# ADRF6780Dev.net
KiCad netlist of a schematic drawn in Altium Designer
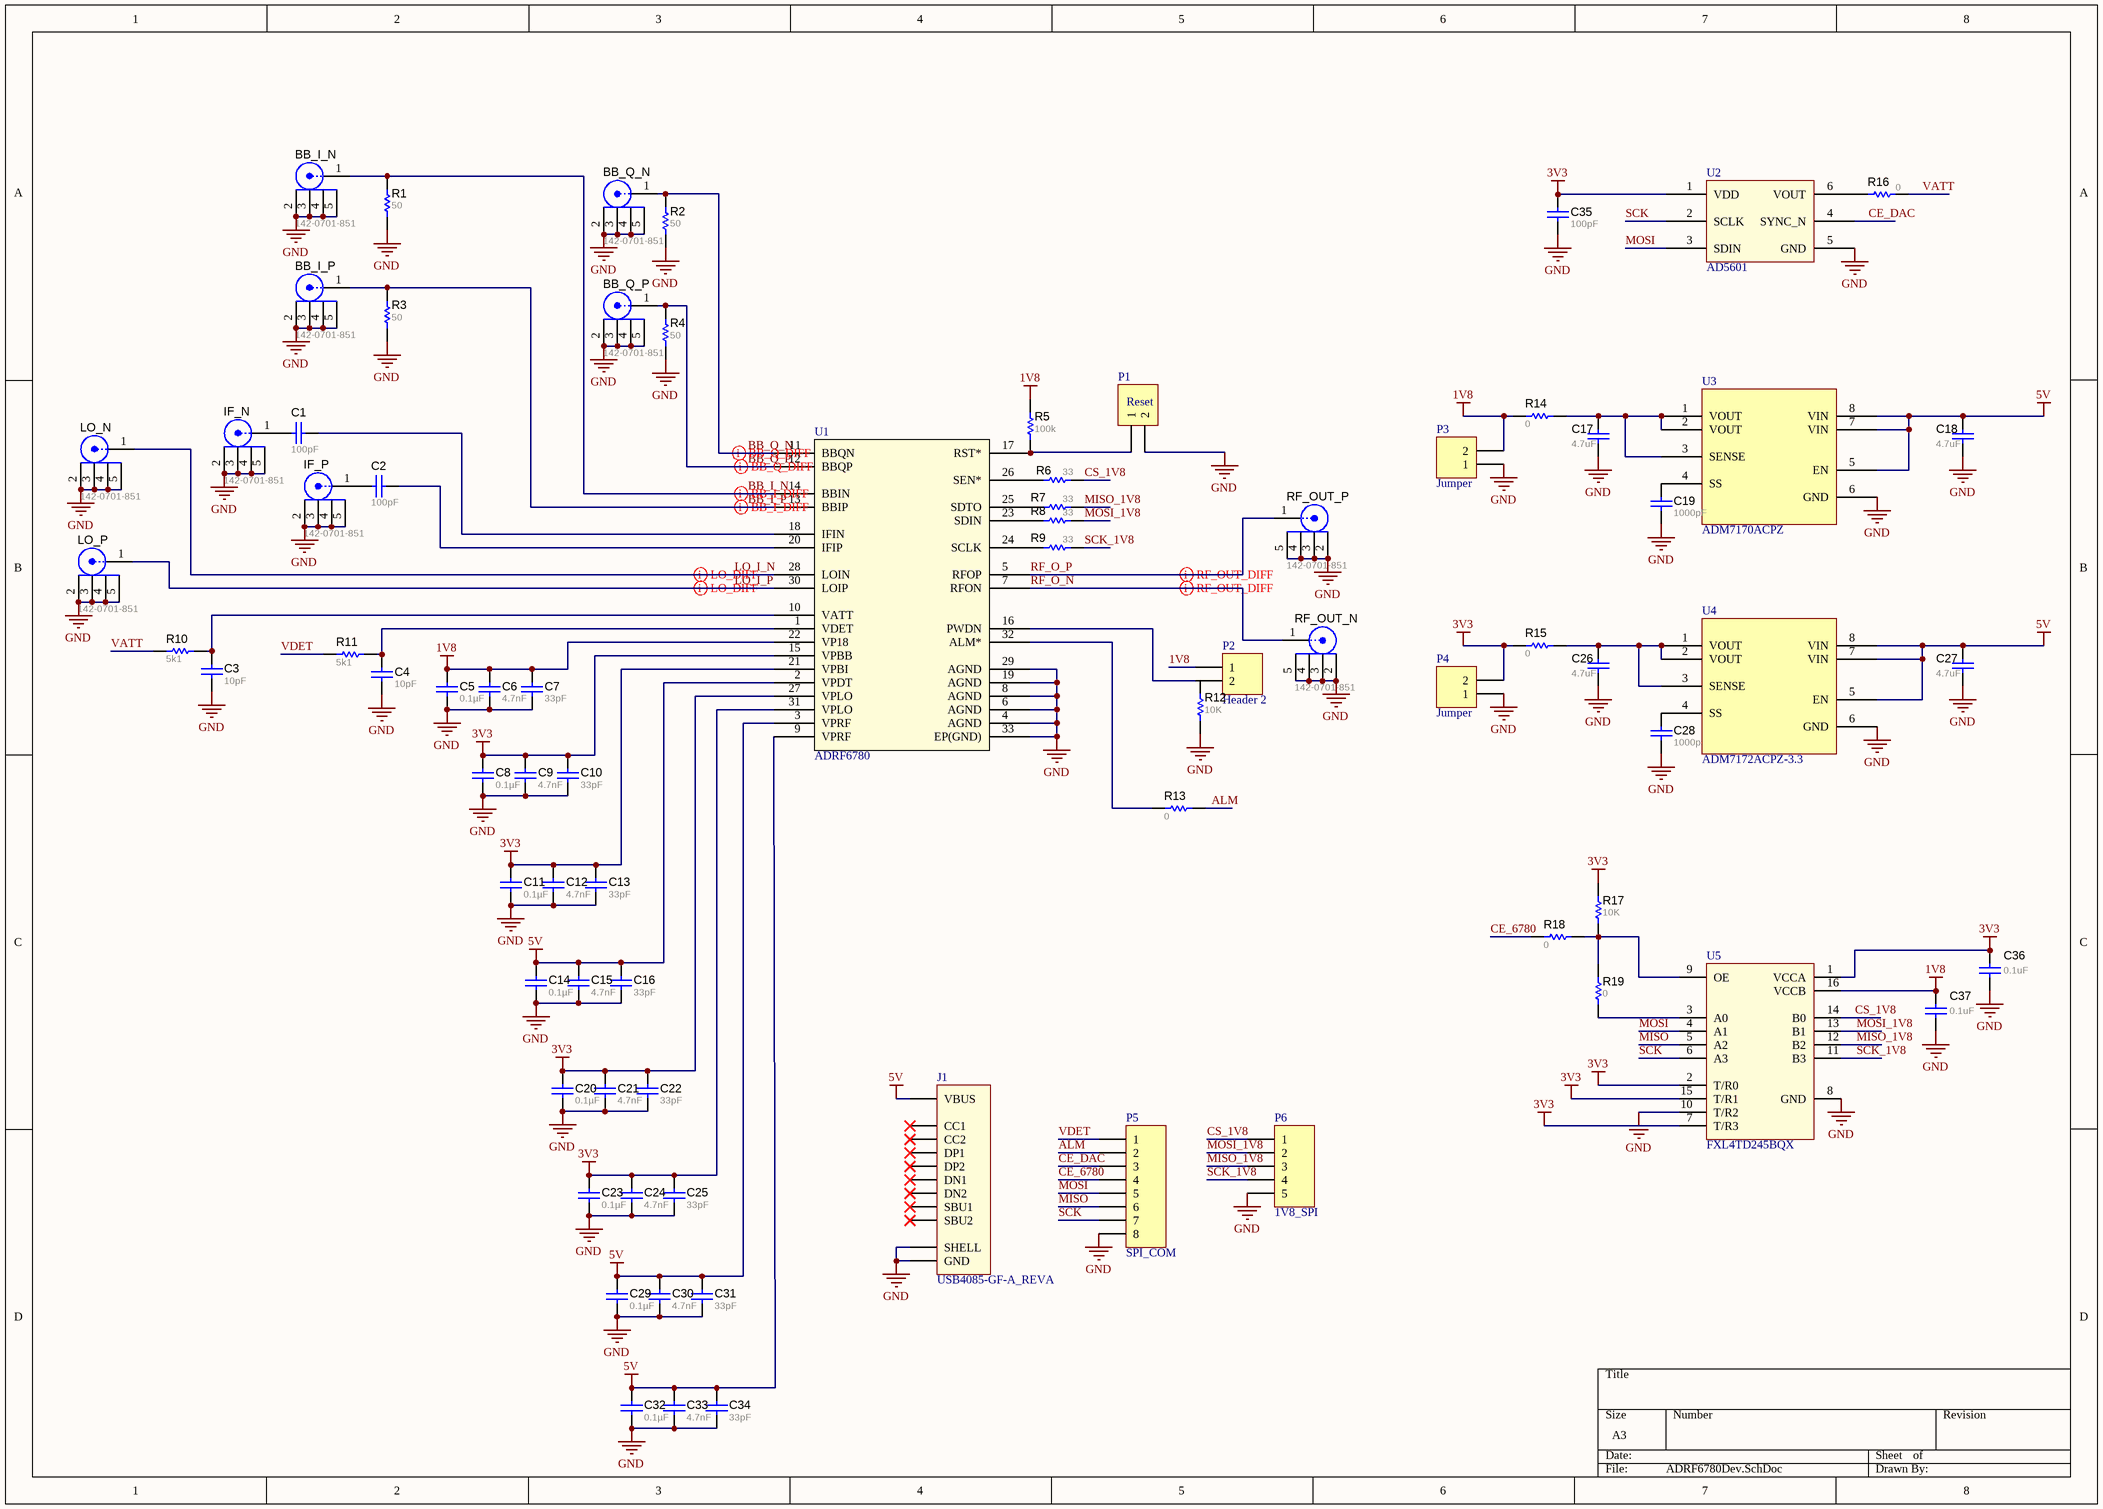
[diagram p0: ADRF6780Dev.SchDoc]

(export (version "E")
  (design (tool "Eeschema 10.0.6"))
  (components
    (comp (ref "BB_I_N")
      (value "142-0701-851")
      (footprint "Emerson_142-0701-851")
      (description "Connector, SMT, End launch SMA 50 ohm")
      (fields
        (field (name "MANUFACTURER") "Emerson Network Power Connectivity")
        (field (name "DIGIKEYPARTNUMBER") "J658-ND")
        (field (name "PUBLISHER") "National Semiconductor")
      )
      (libsource (lib "SV601308") (part "142-0701-851"))
    )
    (comp (ref "BB_I_P")
      (value "142-0701-851")
      (footprint "Emerson_142-0701-851")
      (description "Connector, SMT, End launch SMA 50 ohm")
      (fields
        (field (name "MANUFACTURER") "Emerson Network Power Connectivity")
        (field (name "DIGIKEYPARTNUMBER") "J658-ND")
        (field (name "PUBLISHER") "National Semiconductor")
      )
      (libsource (lib "SV601308") (part "142-0701-851"))
    )
    (comp (ref "BB_Q_N")
      (value "142-0701-851")
      (footprint "Emerson_142-0701-851")
      (description "Connector, SMT, End launch SMA 50 ohm")
      (fields
        (field (name "MANUFACTURER") "Emerson Network Power Connectivity")
        (field (name "DIGIKEYPARTNUMBER") "J658-ND")
        (field (name "PUBLISHER") "National Semiconductor")
      )
      (libsource (lib "SV601308") (part "142-0701-851"))
    )
    (comp (ref "BB_Q_P")
      (value "142-0701-851")
      (footprint "Emerson_142-0701-851")
      (description "Connector, SMT, End launch SMA 50 ohm")
      (fields
        (field (name "MANUFACTURER") "Emerson Network Power Connectivity")
        (field (name "DIGIKEYPARTNUMBER") "J658-ND")
        (field (name "PUBLISHER") "National Semiconductor")
      )
      (libsource (lib "SV601308") (part "142-0701-851"))
    )
    (comp (ref "C1")
      (value "C0603C101J5GACTU")
      (footprint "0603")
      (description "CAP, CERM, 100 pF, 50 V, +/- 5%, C0G/NP0, 0603")
      (fields
        (field (name "MANUFACTURER") "Kemet")
        (field (name "VALUEDISPLAYED") "100pF")
        (field (name "PUBLISHER") "Texas Instruments")
      )
      (libsource (lib "SV601308") (part "C0603C101J5GACTU"))
    )
    (comp (ref "C2")
      (value "C0603C101J5GACTU")
      (footprint "0603")
      (description "CAP, CERM, 100 pF, 50 V, +/- 5%, C0G/NP0, 0603")
      (fields
        (field (name "MANUFACTURER") "Kemet")
        (field (name "VALUEDISPLAYED") "100pF")
        (field (name "PUBLISHER") "Texas Instruments")
      )
      (libsource (lib "SV601308") (part "C0603C101J5GACTU"))
    )
    (comp (ref "C3")
      (value "C1608X5R1A106M080AC")
      (footprint "0603")
      (description "CAP, CERM, 10 µF, 10 V, +/- 20%, X5R, 0603")
      (fields
        (field (name "MANUFACTURER") "TDK")
        (field (name "VALUEDISPLAYED") "10pF")
        (field (name "PUBLISHER") "Texas Instruments")
      )
      (libsource (lib "SV601308") (part "C1608X5R1A106M080AC"))
    )
    (comp (ref "C4")
      (value "C1608X5R1A106M080AC")
      (footprint "0603")
      (description "CAP, CERM, 10 µF, 10 V, +/- 20%, X5R, 0603")
      (fields
        (field (name "MANUFACTURER") "TDK")
        (field (name "VALUEDISPLAYED") "10pF")
        (field (name "PUBLISHER") "Texas Instruments")
      )
      (libsource (lib "SV601308") (part "C1608X5R1A106M080AC"))
    )
    (comp (ref "C5")
      (value "C1608X5R1A106M080AC")
      (footprint "0603")
      (description "CAP, CERM, 10 µF, 10 V, +/- 20%, X5R, 0603")
      (fields
        (field (name "MANUFACTURER") "TDK")
        (field (name "VALUEDISPLAYED") "0.1µF")
        (field (name "PUBLISHER") "Texas Instruments")
      )
      (libsource (lib "SV601308") (part "C1608X5R1A106M080AC"))
    )
    (comp (ref "C6")
      (value "C1608X5R1A106M080AC")
      (footprint "0603")
      (description "CAP, CERM, 10 µF, 10 V, +/- 20%, X5R, 0603")
      (fields
        (field (name "MANUFACTURER") "TDK")
        (field (name "VALUEDISPLAYED") "4.7nF")
        (field (name "PUBLISHER") "Texas Instruments")
      )
      (libsource (lib "SV601308") (part "C1608X5R1A106M080AC"))
    )
    (comp (ref "C7")
      (value "C1608X5R1A106M080AC")
      (footprint "0603")
      (description "CAP, CERM, 10 µF, 10 V, +/- 20%, X5R, 0603")
      (fields
        (field (name "MANUFACTURER") "TDK")
        (field (name "VALUEDISPLAYED") "33pF")
        (field (name "PUBLISHER") "Texas Instruments")
      )
      (libsource (lib "SV601308") (part "C1608X5R1A106M080AC"))
    )
    (comp (ref "C8")
      (value "C1608X5R1A106M080AC")
      (footprint "0603")
      (description "CAP, CERM, 10 µF, 10 V, +/- 20%, X5R, 0603")
      (fields
        (field (name "MANUFACTURER") "TDK")
        (field (name "VALUEDISPLAYED") "0.1µF")
        (field (name "PUBLISHER") "Texas Instruments")
      )
      (libsource (lib "SV601308") (part "C1608X5R1A106M080AC"))
    )
    (comp (ref "C9")
      (value "C1608X5R1A106M080AC")
      (footprint "0603")
      (description "CAP, CERM, 10 µF, 10 V, +/- 20%, X5R, 0603")
      (fields
        (field (name "MANUFACTURER") "TDK")
        (field (name "VALUEDISPLAYED") "4.7nF")
        (field (name "PUBLISHER") "Texas Instruments")
      )
      (libsource (lib "SV601308") (part "C1608X5R1A106M080AC"))
    )
    (comp (ref "C10")
      (value "C1608X5R1A106M080AC")
      (footprint "0603")
      (description "CAP, CERM, 10 µF, 10 V, +/- 20%, X5R, 0603")
      (fields
        (field (name "MANUFACTURER") "TDK")
        (field (name "VALUEDISPLAYED") "33pF")
        (field (name "PUBLISHER") "Texas Instruments")
      )
      (libsource (lib "SV601308") (part "C1608X5R1A106M080AC"))
    )
    (comp (ref "C11")
      (value "C1608X5R1A106M080AC")
      (footprint "0603")
      (description "CAP, CERM, 10 µF, 10 V, +/- 20%, X5R, 0603")
      (fields
        (field (name "MANUFACTURER") "TDK")
        (field (name "VALUEDISPLAYED") "0.1µF")
        (field (name "PUBLISHER") "Texas Instruments")
      )
      (libsource (lib "SV601308") (part "C1608X5R1A106M080AC"))
    )
    (comp (ref "C12")
      (value "C1608X5R1A106M080AC")
      (footprint "0603")
      (description "CAP, CERM, 10 µF, 10 V, +/- 20%, X5R, 0603")
      (fields
        (field (name "MANUFACTURER") "TDK")
        (field (name "VALUEDISPLAYED") "4.7nF")
        (field (name "PUBLISHER") "Texas Instruments")
      )
      (libsource (lib "SV601308") (part "C1608X5R1A106M080AC"))
    )
    (comp (ref "C13")
      (value "C1608X5R1A106M080AC")
      (footprint "0603")
      (description "CAP, CERM, 10 µF, 10 V, +/- 20%, X5R, 0603")
      (fields
        (field (name "MANUFACTURER") "TDK")
        (field (name "VALUEDISPLAYED") "33pF")
        (field (name "PUBLISHER") "Texas Instruments")
      )
      (libsource (lib "SV601308") (part "C1608X5R1A106M080AC"))
    )
    (comp (ref "C14")
      (value "C1608X5R1A106M080AC")
      (footprint "0603")
      (description "CAP, CERM, 10 µF, 10 V, +/- 20%, X5R, 0603")
      (fields
        (field (name "MANUFACTURER") "TDK")
        (field (name "VALUEDISPLAYED") "0.1µF")
        (field (name "PUBLISHER") "Texas Instruments")
      )
      (libsource (lib "SV601308") (part "C1608X5R1A106M080AC"))
    )
    (comp (ref "C15")
      (value "C1608X5R1A106M080AC")
      (footprint "0603")
      (description "CAP, CERM, 10 µF, 10 V, +/- 20%, X5R, 0603")
      (fields
        (field (name "MANUFACTURER") "TDK")
        (field (name "VALUEDISPLAYED") "4.7nF")
        (field (name "PUBLISHER") "Texas Instruments")
      )
      (libsource (lib "SV601308") (part "C1608X5R1A106M080AC"))
    )
    (comp (ref "C16")
      (value "C1608X5R1A106M080AC")
      (footprint "0603")
      (description "CAP, CERM, 10 µF, 10 V, +/- 20%, X5R, 0603")
      (fields
        (field (name "MANUFACTURER") "TDK")
        (field (name "VALUEDISPLAYED") "33pF")
        (field (name "PUBLISHER") "Texas Instruments")
      )
      (libsource (lib "SV601308") (part "C1608X5R1A106M080AC"))
    )
    (comp (ref "C17")
      (value "C0603C472J5RACTU")
      (footprint "0603")
      (description "CAP, CERM, 4700 pF, 50 V, +/- 5%, X7R, 0603")
      (fields
        (field (name "MANUFACTURER") "Kemet")
        (field (name "VALUEDISPLAYED") "4.7uF")
        (field (name "PUBLISHER") "Texas Instruments")
      )
      (libsource (lib "SV601308") (part "C0603C472J5RACTU"))
    )
    (comp (ref "C18")
      (value "C0603C472J5RACTU")
      (footprint "0603")
      (description "CAP, CERM, 4700 pF, 50 V, +/- 5%, X7R, 0603")
      (fields
        (field (name "MANUFACTURER") "Kemet")
        (field (name "VALUEDISPLAYED") "4.7uF")
        (field (name "PUBLISHER") "Texas Instruments")
      )
      (libsource (lib "SV601308") (part "C0603C472J5RACTU"))
    )
    (comp (ref "C19")
      (value "C0603C472J5RACTU")
      (footprint "0603")
      (description "CAP, CERM, 4700 pF, 50 V, +/- 5%, X7R, 0603")
      (fields
        (field (name "MANUFACTURER") "Kemet")
        (field (name "VALUEDISPLAYED") "1000pF")
        (field (name "PUBLISHER") "Texas Instruments")
      )
      (libsource (lib "SV601308") (part "C0603C472J5RACTU"))
    )
    (comp (ref "C20")
      (value "C1608X5R1A106M080AC")
      (footprint "0603")
      (description "CAP, CERM, 10 µF, 10 V, +/- 20%, X5R, 0603")
      (fields
        (field (name "MANUFACTURER") "TDK")
        (field (name "VALUEDISPLAYED") "0.1µF")
        (field (name "PUBLISHER") "Texas Instruments")
      )
      (libsource (lib "SV601308") (part "C1608X5R1A106M080AC"))
    )
    (comp (ref "C21")
      (value "C1608X5R1A106M080AC")
      (footprint "0603")
      (description "CAP, CERM, 10 µF, 10 V, +/- 20%, X5R, 0603")
      (fields
        (field (name "MANUFACTURER") "TDK")
        (field (name "VALUEDISPLAYED") "4.7nF")
        (field (name "PUBLISHER") "Texas Instruments")
      )
      (libsource (lib "SV601308") (part "C1608X5R1A106M080AC"))
    )
    (comp (ref "C22")
      (value "C1608X5R1A106M080AC")
      (footprint "0603")
      (description "CAP, CERM, 10 µF, 10 V, +/- 20%, X5R, 0603")
      (fields
        (field (name "MANUFACTURER") "TDK")
        (field (name "VALUEDISPLAYED") "33pF")
        (field (name "PUBLISHER") "Texas Instruments")
      )
      (libsource (lib "SV601308") (part "C1608X5R1A106M080AC"))
    )
    (comp (ref "C23")
      (value "C1608X5R1A106M080AC")
      (footprint "0603")
      (description "CAP, CERM, 10 µF, 10 V, +/- 20%, X5R, 0603")
      (fields
        (field (name "MANUFACTURER") "TDK")
        (field (name "VALUEDISPLAYED") "0.1µF")
        (field (name "PUBLISHER") "Texas Instruments")
      )
      (libsource (lib "SV601308") (part "C1608X5R1A106M080AC"))
    )
    (comp (ref "C24")
      (value "C1608X5R1A106M080AC")
      (footprint "0603")
      (description "CAP, CERM, 10 µF, 10 V, +/- 20%, X5R, 0603")
      (fields
        (field (name "MANUFACTURER") "TDK")
        (field (name "VALUEDISPLAYED") "4.7nF")
        (field (name "PUBLISHER") "Texas Instruments")
      )
      (libsource (lib "SV601308") (part "C1608X5R1A106M080AC"))
    )
    (comp (ref "C25")
      (value "C1608X5R1A106M080AC")
      (footprint "0603")
      (description "CAP, CERM, 10 µF, 10 V, +/- 20%, X5R, 0603")
      (fields
        (field (name "MANUFACTURER") "TDK")
        (field (name "VALUEDISPLAYED") "33pF")
        (field (name "PUBLISHER") "Texas Instruments")
      )
      (libsource (lib "SV601308") (part "C1608X5R1A106M080AC"))
    )
    (comp (ref "C26")
      (value "C0603C472J5RACTU")
      (footprint "0603")
      (description "CAP, CERM, 4700 pF, 50 V, +/- 5%, X7R, 0603")
      (fields
        (field (name "MANUFACTURER") "Kemet")
        (field (name "VALUEDISPLAYED") "4.7uF")
        (field (name "PUBLISHER") "Texas Instruments")
      )
      (libsource (lib "SV601308") (part "C0603C472J5RACTU"))
    )
    (comp (ref "C27")
      (value "C0603C472J5RACTU")
      (footprint "0603")
      (description "CAP, CERM, 4700 pF, 50 V, +/- 5%, X7R, 0603")
      (fields
        (field (name "MANUFACTURER") "Kemet")
        (field (name "VALUEDISPLAYED") "4.7uF")
        (field (name "PUBLISHER") "Texas Instruments")
      )
      (libsource (lib "SV601308") (part "C0603C472J5RACTU"))
    )
    (comp (ref "C28")
      (value "C0603C472J5RACTU")
      (footprint "0603")
      (description "CAP, CERM, 4700 pF, 50 V, +/- 5%, X7R, 0603")
      (fields
        (field (name "MANUFACTURER") "Kemet")
        (field (name "VALUEDISPLAYED") "1000pF")
        (field (name "PUBLISHER") "Texas Instruments")
      )
      (libsource (lib "SV601308") (part "C0603C472J5RACTU"))
    )
    (comp (ref "C29")
      (value "C1608X5R1A106M080AC")
      (footprint "0603")
      (description "CAP, CERM, 10 µF, 10 V, +/- 20%, X5R, 0603")
      (fields
        (field (name "MANUFACTURER") "TDK")
        (field (name "VALUEDISPLAYED") "0.1µF")
        (field (name "PUBLISHER") "Texas Instruments")
      )
      (libsource (lib "SV601308") (part "C1608X5R1A106M080AC"))
    )
    (comp (ref "C30")
      (value "C1608X5R1A106M080AC")
      (footprint "0603")
      (description "CAP, CERM, 10 µF, 10 V, +/- 20%, X5R, 0603")
      (fields
        (field (name "MANUFACTURER") "TDK")
        (field (name "VALUEDISPLAYED") "4.7nF")
        (field (name "PUBLISHER") "Texas Instruments")
      )
      (libsource (lib "SV601308") (part "C1608X5R1A106M080AC"))
    )
    (comp (ref "C31")
      (value "C1608X5R1A106M080AC")
      (footprint "0603")
      (description "CAP, CERM, 10 µF, 10 V, +/- 20%, X5R, 0603")
      (fields
        (field (name "MANUFACTURER") "TDK")
        (field (name "VALUEDISPLAYED") "33pF")
        (field (name "PUBLISHER") "Texas Instruments")
      )
      (libsource (lib "SV601308") (part "C1608X5R1A106M080AC"))
    )
    (comp (ref "C32")
      (value "C1608X5R1A106M080AC")
      (footprint "0603")
      (description "CAP, CERM, 10 µF, 10 V, +/- 20%, X5R, 0603")
      (fields
        (field (name "MANUFACTURER") "TDK")
        (field (name "VALUEDISPLAYED") "0.1µF")
        (field (name "PUBLISHER") "Texas Instruments")
      )
      (libsource (lib "SV601308") (part "C1608X5R1A106M080AC"))
    )
    (comp (ref "C33")
      (value "C1608X5R1A106M080AC")
      (footprint "0603")
      (description "CAP, CERM, 10 µF, 10 V, +/- 20%, X5R, 0603")
      (fields
        (field (name "MANUFACTURER") "TDK")
        (field (name "VALUEDISPLAYED") "4.7nF")
        (field (name "PUBLISHER") "Texas Instruments")
      )
      (libsource (lib "SV601308") (part "C1608X5R1A106M080AC"))
    )
    (comp (ref "C34")
      (value "C1608X5R1A106M080AC")
      (footprint "0603")
      (description "CAP, CERM, 10 µF, 10 V, +/- 20%, X5R, 0603")
      (fields
        (field (name "MANUFACTURER") "TDK")
        (field (name "VALUEDISPLAYED") "33pF")
        (field (name "PUBLISHER") "Texas Instruments")
      )
      (libsource (lib "SV601308") (part "C1608X5R1A106M080AC"))
    )
    (comp (ref "C35")
      (value "C0603C101J5GACTU")
      (footprint "0603")
      (description "CAP, CERM, 100 pF, 50 V, +/- 5%, C0G/NP0, 0603")
      (fields
        (field (name "MANUFACTURER") "Kemet")
        (field (name "VALUEDISPLAYED") "100pF")
        (field (name "PUBLISHER") "Texas Instruments")
      )
      (libsource (lib "SV601308") (part "C0603C101J5GACTU"))
    )
    (comp (ref "C36")
      (value "C0603C472J5RACTU")
      (footprint "0603")
      (description "CAP, CERM, 4700 pF, 50 V, +/- 5%, X7R, 0603")
      (fields
        (field (name "MANUFACTURER") "Kemet")
        (field (name "VALUEDISPLAYED") "0.1uF")
        (field (name "PUBLISHER") "Texas Instruments")
      )
      (libsource (lib "SV601308") (part "C0603C472J5RACTU"))
    )
    (comp (ref "C37")
      (value "C0603C472J5RACTU")
      (footprint "0603")
      (description "CAP, CERM, 4700 pF, 50 V, +/- 5%, X7R, 0603")
      (fields
        (field (name "MANUFACTURER") "Kemet")
        (field (name "VALUEDISPLAYED") "0.1uF")
        (field (name "PUBLISHER") "Texas Instruments")
      )
      (libsource (lib "SV601308") (part "C0603C472J5RACTU"))
    )
    (comp (ref "IF_N")
      (value "142-0701-851")
      (footprint "Emerson_142-0701-851")
      (description "Connector, SMT, End launch SMA 50 ohm")
      (fields
        (field (name "MANUFACTURER") "Emerson Network Power Connectivity")
        (field (name "DIGIKEYPARTNUMBER") "J658-ND")
        (field (name "PUBLISHER") "National Semiconductor")
      )
      (libsource (lib "SV601308") (part "142-0701-851"))
    )
    (comp (ref "IF_P")
      (value "142-0701-851")
      (footprint "Emerson_142-0701-851")
      (description "Connector, SMT, End launch SMA 50 ohm")
      (fields
        (field (name "MANUFACTURER") "Emerson Network Power Connectivity")
        (field (name "DIGIKEYPARTNUMBER") "J658-ND")
        (field (name "PUBLISHER") "National Semiconductor")
      )
      (libsource (lib "SV601308") (part "142-0701-851"))
    )
    (comp (ref "J1")
      (value "USB4085-GF-A_REVA")
      (footprint "GCT_USB4085-GF-A_REVA")
      (fields (field (name "MP") "USB4085-GF-A") (field (name "MF") "Global Connector Technology"))
      (libsource (lib "USB4085-GF-A_REVA") (part "USB4085-GF-A_REVA"))
    )
    (comp (ref "LO_N")
      (value "142-0701-851")
      (footprint "Emerson_142-0701-851")
      (description "Connector, SMT, End launch SMA 50 ohm")
      (fields
        (field (name "MANUFACTURER") "Emerson Network Power Connectivity")
        (field (name "DIGIKEYPARTNUMBER") "J658-ND")
        (field (name "PUBLISHER") "National Semiconductor")
      )
      (libsource (lib "SV601308") (part "142-0701-851"))
    )
    (comp (ref "LO_P")
      (value "142-0701-851")
      (footprint "Emerson_142-0701-851")
      (description "Connector, SMT, End launch SMA 50 ohm")
      (fields
        (field (name "MANUFACTURER") "Emerson Network Power Connectivity")
        (field (name "DIGIKEYPARTNUMBER") "J658-ND")
        (field (name "PUBLISHER") "National Semiconductor")
      )
      (libsource (lib "SV601308") (part "142-0701-851"))
    )
    (comp (ref "P1")
      (value "Reset")
      (footprint "HDR1X2")
      (description "Header, 2-Pin")
      (fields (field (name "PUBLISHER") "Altium Limited"))
      (libsource (lib "Miscellaneous Connectors") (part "Header 2"))
    )
    (comp (ref "P2")
      (value "Header 2")
      (footprint "HDR1X2")
      (description "Header, 2-Pin")
      (fields (field (name "PUBLISHER") "Altium Limited"))
      (libsource (lib "") (part "Header 2_2"))
    )
    (comp (ref "P3")
      (value "Jumper")
      (footprint "HDR1X2")
      (description "Header, 2-Pin")
      (fields (field (name "PUBLISHER") "Altium Limited"))
      (libsource (lib "") (part "Header 2_1"))
    )
    (comp (ref "P4")
      (value "Jumper")
      (footprint "HDR1X2")
      (description "Header, 2-Pin")
      (fields (field (name "PUBLISHER") "Altium Limited"))
      (libsource (lib "") (part "Header 2_1"))
    )
    (comp (ref "P5")
      (value "SPI_COM")
      (footprint "HDR1X8")
      (description "Header, 8-Pin")
      (fields (field (name "PUBLISHER") "Altium Limited"))
      (libsource (lib "Miscellaneous Connectors") (part "Header 8"))
    )
    (comp (ref "P6")
      (value "1V8_SPI")
      (footprint "HDR1X5")
      (description "Header, 5-Pin")
      (fields (field (name "PUBLISHER") "Altium Limited"))
      (libsource (lib "Miscellaneous Connectors") (part "Header 5"))
    )
    (comp (ref "R1")
      (value "CRCW0603100KJNEA")
      (footprint "0603")
      (description "RES, 100 k, 5%, 0.1 W, 0603")
      (fields
        (field (name "MANUFACTURER") "Vishay-Dale")
        (field (name "VALUEDISPLAYED") "50")
        (field (name "PUBLISHER") "Texas Instruments")
      )
      (libsource (lib "SV601308") (part "CRCW0603100KJNEA"))
    )
    (comp (ref "R2")
      (value "CRCW0603100KJNEA")
      (footprint "0603")
      (description "RES, 100 k, 5%, 0.1 W, 0603")
      (fields
        (field (name "MANUFACTURER") "Vishay-Dale")
        (field (name "VALUEDISPLAYED") "50")
        (field (name "PUBLISHER") "Texas Instruments")
      )
      (libsource (lib "SV601308") (part "CRCW0603100KJNEA"))
    )
    (comp (ref "R3")
      (value "CRCW0603100KJNEA")
      (footprint "0603")
      (description "RES, 100 k, 5%, 0.1 W, 0603")
      (fields
        (field (name "MANUFACTURER") "Vishay-Dale")
        (field (name "VALUEDISPLAYED") "50")
        (field (name "PUBLISHER") "Texas Instruments")
      )
      (libsource (lib "SV601308") (part "CRCW0603100KJNEA"))
    )
    (comp (ref "R4")
      (value "CRCW0603100KJNEA")
      (footprint "0603")
      (description "RES, 100 k, 5%, 0.1 W, 0603")
      (fields
        (field (name "MANUFACTURER") "Vishay-Dale")
        (field (name "VALUEDISPLAYED") "50")
        (field (name "PUBLISHER") "Texas Instruments")
      )
      (libsource (lib "SV601308") (part "CRCW0603100KJNEA"))
    )
    (comp (ref "R5")
      (value "CRCW0603100KJNEA")
      (footprint "0603")
      (description "RES, 100 k, 5%, 0.1 W, 0603")
      (fields
        (field (name "MANUFACTURER") "Vishay-Dale")
        (field (name "VALUEDISPLAYED") "100k")
        (field (name "PUBLISHER") "Texas Instruments")
      )
      (libsource (lib "SV601308") (part "CRCW0603100KJNEA"))
    )
    (comp (ref "R6")
      (value "CRCW0603100KJNEA")
      (footprint "0603")
      (description "RES, 100 k, 5%, 0.1 W, 0603")
      (fields
        (field (name "MANUFACTURER") "Vishay-Dale")
        (field (name "VALUEDISPLAYED") "33")
        (field (name "PUBLISHER") "Texas Instruments")
      )
      (libsource (lib "SV601308") (part "CRCW0603100KJNEA"))
    )
    (comp (ref "R7")
      (value "CRCW0603100KJNEA")
      (footprint "0603")
      (description "RES, 100 k, 5%, 0.1 W, 0603")
      (fields
        (field (name "MANUFACTURER") "Vishay-Dale")
        (field (name "VALUEDISPLAYED") "33")
        (field (name "PUBLISHER") "Texas Instruments")
      )
      (libsource (lib "SV601308") (part "CRCW0603100KJNEA"))
    )
    (comp (ref "R8")
      (value "CRCW0603100KJNEA")
      (footprint "0603")
      (description "RES, 100 k, 5%, 0.1 W, 0603")
      (fields
        (field (name "MANUFACTURER") "Vishay-Dale")
        (field (name "VALUEDISPLAYED") "33")
        (field (name "PUBLISHER") "Texas Instruments")
      )
      (libsource (lib "SV601308") (part "CRCW0603100KJNEA"))
    )
    (comp (ref "R9")
      (value "CRCW0603100KJNEA")
      (footprint "0603")
      (description "RES, 100 k, 5%, 0.1 W, 0603")
      (fields
        (field (name "MANUFACTURER") "Vishay-Dale")
        (field (name "VALUEDISPLAYED") "33")
        (field (name "PUBLISHER") "Texas Instruments")
      )
      (libsource (lib "SV601308") (part "CRCW0603100KJNEA"))
    )
    (comp (ref "R10")
      (value "CRCW0603100RFKEA")
      (footprint "0603L")
      (description "RES, 100, 1%, 0.1 W, 0603")
      (fields
        (field (name "MANUFACTURER") "Vishay-Dale")
        (field (name "VALUEDISPLAYED") "5k1")
        (field (name "PUBLISHER") "Texas Instruments")
      )
      (libsource (lib "SV601308") (part "CRCW0603100RFKEA"))
    )
    (comp (ref "R11")
      (value "CRCW0603100RFKEA")
      (footprint "0603L")
      (description "RES, 100, 1%, 0.1 W, 0603")
      (fields
        (field (name "MANUFACTURER") "Vishay-Dale")
        (field (name "VALUEDISPLAYED") "5k1")
        (field (name "PUBLISHER") "Texas Instruments")
      )
      (libsource (lib "SV601308") (part "CRCW0603100RFKEA"))
    )
    (comp (ref "R12")
      (value "CRCW0603100KJNEA")
      (footprint "0603")
      (description "RES, 100 k, 5%, 0.1 W, 0603")
      (fields
        (field (name "MANUFACTURER") "Vishay-Dale")
        (field (name "VALUEDISPLAYED") "10K")
        (field (name "PUBLISHER") "Texas Instruments")
      )
      (libsource (lib "SV601308") (part "CRCW0603100KJNEA"))
    )
    (comp (ref "R13")
      (value "CRCW0603100KJNEA")
      (footprint "0603")
      (description "RES, 100 k, 5%, 0.1 W, 0603")
      (fields
        (field (name "MANUFACTURER") "Vishay-Dale")
        (field (name "VALUEDISPLAYED") "0")
        (field (name "PUBLISHER") "Texas Instruments")
      )
      (libsource (lib "SV601308") (part "CRCW0603100KJNEA"))
    )
    (comp (ref "R14")
      (value "CRCW06030000Z0EA")
      (footprint "0603")
      (description "RES, 0, 5%, 0.1 W, 0603")
      (fields
        (field (name "MANUFACTURER") "Vishay-Dale")
        (field (name "VALUEDISPLAYED") "0")
        (field (name "PUBLISHER") "Texas Instruments")
      )
      (libsource (lib "SV601308") (part "CRCW06030000Z0EA"))
    )
    (comp (ref "R15")
      (value "CRCW06030000Z0EA")
      (footprint "0603")
      (description "RES, 0, 5%, 0.1 W, 0603")
      (fields
        (field (name "MANUFACTURER") "Vishay-Dale")
        (field (name "VALUEDISPLAYED") "0")
        (field (name "PUBLISHER") "Texas Instruments")
      )
      (libsource (lib "SV601308") (part "CRCW06030000Z0EA"))
    )
    (comp (ref "R16")
      (value "CRCW0603100KJNEA")
      (footprint "0603")
      (description "RES, 100 k, 5%, 0.1 W, 0603")
      (fields
        (field (name "MANUFACTURER") "Vishay-Dale")
        (field (name "VALUEDISPLAYED") "0")
        (field (name "PUBLISHER") "Texas Instruments")
      )
      (libsource (lib "SV601308") (part "CRCW0603100KJNEA"))
    )
    (comp (ref "R17")
      (value "CRCW06030000Z0EA")
      (footprint "0603")
      (description "RES, 0, 5%, 0.1 W, 0603")
      (fields
        (field (name "MANUFACTURER") "Vishay-Dale")
        (field (name "VALUEDISPLAYED") "10K")
        (field (name "PUBLISHER") "Texas Instruments")
      )
      (libsource (lib "SV601308") (part "CRCW06030000Z0EA"))
    )
    (comp (ref "R18")
      (value "CRCW06030000Z0EA")
      (footprint "0603")
      (description "RES, 0, 5%, 0.1 W, 0603")
      (fields
        (field (name "MANUFACTURER") "Vishay-Dale")
        (field (name "VALUEDISPLAYED") "0")
        (field (name "PUBLISHER") "Texas Instruments")
      )
      (libsource (lib "SV601308") (part "CRCW06030000Z0EA"))
    )
    (comp (ref "R19")
      (value "CRCW06030000Z0EA")
      (footprint "0603")
      (description "RES, 0, 5%, 0.1 W, 0603")
      (fields
        (field (name "MANUFACTURER") "Vishay-Dale")
        (field (name "VALUEDISPLAYED") "0")
        (field (name "PUBLISHER") "Texas Instruments")
      )
      (libsource (lib "SV601308") (part "CRCW06030000Z0EA"))
    )
    (comp (ref "RF_OUT_N")
      (value "142-0701-851")
      (footprint "Emerson_142-0701-851")
      (description "Connector, SMT, End launch SMA 50 ohm")
      (fields
        (field (name "MANUFACTURER") "Emerson Network Power Connectivity")
        (field (name "DIGIKEYPARTNUMBER") "J658-ND")
        (field (name "PUBLISHER") "National Semiconductor")
      )
      (libsource (lib "SV601308") (part "142-0701-851"))
    )
    (comp (ref "RF_OUT_P")
      (value "142-0701-851")
      (footprint "Emerson_142-0701-851")
      (description "Connector, SMT, End launch SMA 50 ohm")
      (fields
        (field (name "MANUFACTURER") "Emerson Network Power Connectivity")
        (field (name "DIGIKEYPARTNUMBER") "J658-ND")
        (field (name "PUBLISHER") "National Semiconductor")
      )
      (libsource (lib "SV601308") (part "142-0701-851"))
    )
    (comp (ref "U1") (value "ADRF6780") (footprint "ADRF6780") (libsource (lib "rf") (part "ADRF6780")))
    (comp (ref "U2")
      (value "AD5601")
      (footprint "AD5601/AD5611/AD5621")
      (description "2.7 V to 5.5 V, <100 μA, 8-/10-/12-Bit\r\nnanoDAC, SPI Interface in SC70")
      (libsource (lib "rf") (part "AD5601"))
    )
    (comp (ref "U3")
      (value "ADM7170ACPZ")
      (footprint "ADM7170ACPZ")
      (description "500 mA, Ultralow Noise, High PSRR,\r\nFast Transient Response CMOS LDO")
      (libsource (lib "rf") (part "ADM7170ACPZ"))
    )
    (comp (ref "U4")
      (value "ADM7172ACPZ-3.3")
      (footprint "ADM7170ACPZ")
      (libsource (lib "rf") (part "ADM7172ACPZ-3.3"))
    )
    (comp (ref "U5")
      (value "FXL4TD245BQX")
      (footprint "DQFN-16")
      (description "Voltage Level Translator Bidirectional 1 Circuit 4 Channel 16-DQFN (2.5x3.5)")
      (fields (field (name "MF") "ON Semiconductor"))
      (libsource (lib "FXL4TD245BQX") (part "FXL4TD245BQX"))
    )
  )
  (nets
    (net (code "1") (name "/ALM") (class "Default")
      (node (ref "P5") (pin "2") (pinfunction "2_2") (pintype "passive"))
      (node (ref "R13") (pin "2") (pinfunction "2_2") (pintype "passive"))
    )
    (net (code "2") (name "/BB_I_N") (class "Default")
      (node (ref "BB_I_N") (pin "1") (pinfunction "1_1") (pintype "passive"))
      (node (ref "R1") (pin "2") (pinfunction "2_2") (pintype "passive"))
      (node (ref "U1") (pin "14") (pinfunction "BBIN_14") (pintype "passive"))
    )
    (net (code "3") (name "/BB_I_P") (class "Default")
      (node (ref "BB_I_P") (pin "1") (pinfunction "1_1") (pintype "passive"))
      (node (ref "R3") (pin "2") (pinfunction "2_2") (pintype "passive"))
      (node (ref "U1") (pin "13") (pinfunction "BBIP_13") (pintype "passive"))
    )
    (net (code "4") (name "/BB_Q_N") (class "Default")
      (node (ref "BB_Q_N") (pin "1") (pinfunction "1_1") (pintype "passive"))
      (node (ref "R2") (pin "2") (pinfunction "2_2") (pintype "passive"))
      (node (ref "U1") (pin "11") (pinfunction "BBQN_11") (pintype "passive"))
    )
    (net (code "5") (name "/BB_Q_P") (class "Default")
      (node (ref "BB_Q_P") (pin "1") (pinfunction "1_1") (pintype "passive"))
      (node (ref "R4") (pin "2") (pinfunction "2_2") (pintype "passive"))
      (node (ref "U1") (pin "12") (pinfunction "BBQP_12") (pintype "passive"))
    )
    (net (code "6") (name "/CE_6780") (class "Default")
      (node (ref "P5") (pin "4") (pinfunction "4_4") (pintype "passive"))
      (node (ref "R18") (pin "2") (pinfunction "2_2") (pintype "passive"))
    )
    (net (code "7") (name "/CE_DAC") (class "Default")
      (node (ref "P5") (pin "3") (pinfunction "3_3") (pintype "passive"))
      (node (ref "U2") (pin "4") (pinfunction "SYNC_N_4") (pintype "passive"))
    )
    (net (code "8") (name "/CS_1V8") (class "Default")
      (node (ref "P6") (pin "1") (pinfunction "1_1") (pintype "passive"))
      (node (ref "R6") (pin "2") (pinfunction "2_2") (pintype "passive"))
      (node (ref "U5") (pin "14") (pinfunction "B0_14") (pintype "passive"))
    )
    (net (code "9") (name "/LO_I_N") (class "Default")
      (node (ref "LO_N") (pin "1") (pinfunction "1_1") (pintype "passive"))
      (node (ref "U1") (pin "28") (pinfunction "LOIN_28") (pintype "passive"))
    )
    (net (code "10") (name "/LO_I_P") (class "Default")
      (node (ref "LO_P") (pin "1") (pinfunction "1_1") (pintype "passive"))
      (node (ref "U1") (pin "30") (pinfunction "LOIP_30") (pintype "passive"))
    )
    (net (code "11") (name "/MISO") (class "Default")
      (node (ref "P5") (pin "6") (pinfunction "6_6") (pintype "passive"))
      (node (ref "U5") (pin "5") (pinfunction "A2_5") (pintype "passive"))
    )
    (net (code "12") (name "/MISO_1V8") (class "Default")
      (node (ref "P6") (pin "3") (pinfunction "3_3") (pintype "passive"))
      (node (ref "R7") (pin "2") (pinfunction "2_2") (pintype "passive"))
      (node (ref "U5") (pin "12") (pinfunction "B2_12") (pintype "passive"))
    )
    (net (code "13") (name "/MOSI") (class "Default")
      (node (ref "P5") (pin "5") (pinfunction "5_5") (pintype "passive"))
      (node (ref "U2") (pin "3") (pinfunction "SDIN_3") (pintype "passive"))
      (node (ref "U5") (pin "4") (pinfunction "A1_4") (pintype "passive"))
    )
    (net (code "14") (name "/MOSI_1V8") (class "Default")
      (node (ref "P6") (pin "2") (pinfunction "2_2") (pintype "passive"))
      (node (ref "R8") (pin "2") (pinfunction "2_2") (pintype "passive"))
      (node (ref "U5") (pin "13") (pinfunction "B1_13") (pintype "passive"))
    )
    (net (code "15") (name "/RF_O_N") (class "Default")
      (node (ref "RF_OUT_N") (pin "1") (pinfunction "1_1") (pintype "passive"))
      (node (ref "U1") (pin "7") (pinfunction "RFON_7") (pintype "passive"))
    )
    (net (code "16") (name "/RF_O_P") (class "Default")
      (node (ref "RF_OUT_P") (pin "1") (pinfunction "1_1") (pintype "passive"))
      (node (ref "U1") (pin "5") (pinfunction "RFOP_5") (pintype "passive"))
    )
    (net (code "17") (name "/SCK") (class "Default")
      (node (ref "P5") (pin "7") (pinfunction "7_7") (pintype "passive"))
      (node (ref "U2") (pin "2") (pinfunction "SCLK_2") (pintype "passive"))
      (node (ref "U5") (pin "6") (pinfunction "A3_6") (pintype "passive"))
    )
    (net (code "18") (name "/SCK_1V8") (class "Default")
      (node (ref "P6") (pin "4") (pinfunction "4_4") (pintype "passive"))
      (node (ref "R9") (pin "2") (pinfunction "2_2") (pintype "passive"))
      (node (ref "U5") (pin "11") (pinfunction "B3_11") (pintype "passive"))
    )
    (net (code "19") (name "/VATT") (class "Default")
      (node (ref "R10") (pin "1") (pinfunction "1_1") (pintype "passive"))
      (node (ref "R16") (pin "1") (pinfunction "1_1") (pintype "passive"))
    )
    (net (code "20") (name "/VDET") (class "Default")
      (node (ref "P5") (pin "1") (pinfunction "1_1") (pintype "passive"))
      (node (ref "R11") (pin "1") (pinfunction "1_1") (pintype "passive"))
    )
    (net (code "21") (name "1V8") (class "Default")
      (node (ref "C37") (pin "1") (pinfunction "1_1") (pintype "passive"))
      (node (ref "C5") (pin "1") (pinfunction "1_1") (pintype "passive"))
      (node (ref "C6") (pin "1") (pinfunction "1_1") (pintype "passive"))
      (node (ref "C7") (pin "1") (pinfunction "1_1") (pintype "passive"))
      (node (ref "P2") (pin "1") (pinfunction "1_1") (pintype "passive"))
      (node (ref "P3") (pin "2") (pinfunction "2_2") (pintype "passive"))
      (node (ref "R14") (pin "1") (pinfunction "1_1") (pintype "passive"))
      (node (ref "R5") (pin "2") (pinfunction "2_2") (pintype "passive"))
      (node (ref "U1") (pin "22") (pinfunction "VP18_22") (pintype "passive"))
      (node (ref "U5") (pin "16") (pinfunction "VCCB_16") (pintype "power_in"))
    )
    (net (code "22") (name "3V3") (class "Default")
      (node (ref "C10") (pin "1") (pinfunction "1_1") (pintype "passive"))
      (node (ref "C11") (pin "1") (pinfunction "1_1") (pintype "passive"))
      (node (ref "C12") (pin "1") (pinfunction "1_1") (pintype "passive"))
      (node (ref "C13") (pin "1") (pinfunction "1_1") (pintype "passive"))
      (node (ref "C20") (pin "1") (pinfunction "1_1") (pintype "passive"))
      (node (ref "C21") (pin "1") (pinfunction "1_1") (pintype "passive"))
      (node (ref "C22") (pin "1") (pinfunction "1_1") (pintype "passive"))
      (node (ref "C23") (pin "1") (pinfunction "1_1") (pintype "passive"))
      (node (ref "C24") (pin "1") (pinfunction "1_1") (pintype "passive"))
      (node (ref "C25") (pin "1") (pinfunction "1_1") (pintype "passive"))
      (node (ref "C35") (pin "1") (pinfunction "1_1") (pintype "passive"))
      (node (ref "C36") (pin "1") (pinfunction "1_1") (pintype "passive"))
      (node (ref "C8") (pin "1") (pinfunction "1_1") (pintype "passive"))
      (node (ref "C9") (pin "1") (pinfunction "1_1") (pintype "passive"))
      (node (ref "P4") (pin "2") (pinfunction "2_2") (pintype "passive"))
      (node (ref "R15") (pin "1") (pinfunction "1_1") (pintype "passive"))
      (node (ref "R17") (pin "2") (pinfunction "2_2") (pintype "passive"))
      (node (ref "U1") (pin "15") (pinfunction "VPBB_15") (pintype "passive"))
      (node (ref "U1") (pin "21") (pinfunction "VPBI_21") (pintype "passive"))
      (node (ref "U1") (pin "27") (pinfunction "VPLO_27") (pintype "passive"))
      (node (ref "U1") (pin "31") (pinfunction "VPLO_31") (pintype "passive"))
      (node (ref "U2") (pin "1") (pinfunction "VDD_1") (pintype "passive"))
      (node (ref "U5") (pin "1") (pinfunction "VCCA_1") (pintype "power_in"))
      (node (ref "U5") (pin "15") (pinfunction "T/R1_15") (pintype "passive"))
      (node (ref "U5") (pin "2") (pinfunction "T/R0_2") (pintype "passive"))
      (node (ref "U5") (pin "7") (pinfunction "T/R3_7") (pintype "passive"))
    )
    (net (code "23") (name "5V") (class "Default")
      (node (ref "C14") (pin "1") (pinfunction "1_1") (pintype "passive"))
      (node (ref "C15") (pin "1") (pinfunction "1_1") (pintype "passive"))
      (node (ref "C16") (pin "1") (pinfunction "1_1") (pintype "passive"))
      (node (ref "C18") (pin "1") (pinfunction "1_1") (pintype "passive"))
      (node (ref "C27") (pin "1") (pinfunction "1_1") (pintype "passive"))
      (node (ref "C29") (pin "1") (pinfunction "1_1") (pintype "passive"))
      (node (ref "C30") (pin "1") (pinfunction "1_1") (pintype "passive"))
      (node (ref "C31") (pin "1") (pinfunction "1_1") (pintype "passive"))
      (node (ref "C32") (pin "1") (pinfunction "1_1") (pintype "passive"))
      (node (ref "C33") (pin "1") (pinfunction "1_1") (pintype "passive"))
      (node (ref "C34") (pin "1") (pinfunction "1_1") (pintype "passive"))
      (node (ref "J1") (pin "V") (pinfunction "VBUS_V") (pintype "power_in"))
      (node (ref "U1") (pin "2") (pinfunction "VPDT_2") (pintype "passive"))
      (node (ref "U1") (pin "3") (pinfunction "VPRF_3") (pintype "passive"))
      (node (ref "U1") (pin "9") (pinfunction "VPRF_9") (pintype "passive"))
      (node (ref "U3") (pin "5") (pinfunction "EN_5") (pintype "passive"))
      (node (ref "U3") (pin "7") (pinfunction "VIN_7") (pintype "passive"))
      (node (ref "U3") (pin "8") (pinfunction "VIN_8") (pintype "passive"))
      (node (ref "U4") (pin "5") (pinfunction "EN_5") (pintype "passive"))
      (node (ref "U4") (pin "7") (pinfunction "VIN_7") (pintype "passive"))
      (node (ref "U4") (pin "8") (pinfunction "VIN_8") (pintype "passive"))
    )
    (net (code "24") (name "GND") (class "Default")
      (node (ref "BB_I_N") (pin "2") (pinfunction "2_2") (pintype "passive"))
      (node (ref "BB_I_N") (pin "3") (pinfunction "3_3") (pintype "passive"))
      (node (ref "BB_I_N") (pin "4") (pinfunction "4_4") (pintype "passive"))
      (node (ref "BB_I_N") (pin "5") (pinfunction "5_5") (pintype "passive"))
      (node (ref "BB_I_P") (pin "2") (pinfunction "2_2") (pintype "passive"))
      (node (ref "BB_I_P") (pin "3") (pinfunction "3_3") (pintype "passive"))
      (node (ref "BB_I_P") (pin "4") (pinfunction "4_4") (pintype "passive"))
      (node (ref "BB_I_P") (pin "5") (pinfunction "5_5") (pintype "passive"))
      (node (ref "BB_Q_N") (pin "2") (pinfunction "2_2") (pintype "passive"))
      (node (ref "BB_Q_N") (pin "3") (pinfunction "3_3") (pintype "passive"))
      (node (ref "BB_Q_N") (pin "4") (pinfunction "4_4") (pintype "passive"))
      (node (ref "BB_Q_N") (pin "5") (pinfunction "5_5") (pintype "passive"))
      (node (ref "BB_Q_P") (pin "2") (pinfunction "2_2") (pintype "passive"))
      (node (ref "BB_Q_P") (pin "3") (pinfunction "3_3") (pintype "passive"))
      (node (ref "BB_Q_P") (pin "4") (pinfunction "4_4") (pintype "passive"))
      (node (ref "BB_Q_P") (pin "5") (pinfunction "5_5") (pintype "passive"))
      (node (ref "C10") (pin "2") (pinfunction "2_2") (pintype "passive"))
      (node (ref "C11") (pin "2") (pinfunction "2_2") (pintype "passive"))
      (node (ref "C12") (pin "2") (pinfunction "2_2") (pintype "passive"))
      (node (ref "C13") (pin "2") (pinfunction "2_2") (pintype "passive"))
      (node (ref "C14") (pin "2") (pinfunction "2_2") (pintype "passive"))
      (node (ref "C15") (pin "2") (pinfunction "2_2") (pintype "passive"))
      (node (ref "C16") (pin "2") (pinfunction "2_2") (pintype "passive"))
      (node (ref "C17") (pin "2") (pinfunction "2_2") (pintype "passive"))
      (node (ref "C18") (pin "2") (pinfunction "2_2") (pintype "passive"))
      (node (ref "C19") (pin "2") (pinfunction "2_2") (pintype "passive"))
      (node (ref "C20") (pin "2") (pinfunction "2_2") (pintype "passive"))
      (node (ref "C21") (pin "2") (pinfunction "2_2") (pintype "passive"))
      (node (ref "C22") (pin "2") (pinfunction "2_2") (pintype "passive"))
      (node (ref "C23") (pin "2") (pinfunction "2_2") (pintype "passive"))
      (node (ref "C24") (pin "2") (pinfunction "2_2") (pintype "passive"))
      (node (ref "C25") (pin "2") (pinfunction "2_2") (pintype "passive"))
      (node (ref "C26") (pin "2") (pinfunction "2_2") (pintype "passive"))
      (node (ref "C27") (pin "2") (pinfunction "2_2") (pintype "passive"))
      (node (ref "C28") (pin "2") (pinfunction "2_2") (pintype "passive"))
      (node (ref "C29") (pin "2") (pinfunction "2_2") (pintype "passive"))
      (node (ref "C3") (pin "2") (pinfunction "2_2") (pintype "passive"))
      (node (ref "C30") (pin "2") (pinfunction "2_2") (pintype "passive"))
      (node (ref "C31") (pin "2") (pinfunction "2_2") (pintype "passive"))
      (node (ref "C32") (pin "2") (pinfunction "2_2") (pintype "passive"))
      (node (ref "C33") (pin "2") (pinfunction "2_2") (pintype "passive"))
      (node (ref "C34") (pin "2") (pinfunction "2_2") (pintype "passive"))
      (node (ref "C35") (pin "2") (pinfunction "2_2") (pintype "passive"))
      (node (ref "C36") (pin "2") (pinfunction "2_2") (pintype "passive"))
      (node (ref "C37") (pin "2") (pinfunction "2_2") (pintype "passive"))
      (node (ref "C4") (pin "2") (pinfunction "2_2") (pintype "passive"))
      (node (ref "C5") (pin "2") (pinfunction "2_2") (pintype "passive"))
      (node (ref "C6") (pin "2") (pinfunction "2_2") (pintype "passive"))
      (node (ref "C7") (pin "2") (pinfunction "2_2") (pintype "passive"))
      (node (ref "C8") (pin "2") (pinfunction "2_2") (pintype "passive"))
      (node (ref "C9") (pin "2") (pinfunction "2_2") (pintype "passive"))
      (node (ref "IF_N") (pin "2") (pinfunction "2_2") (pintype "passive"))
      (node (ref "IF_N") (pin "3") (pinfunction "3_3") (pintype "passive"))
      (node (ref "IF_N") (pin "4") (pinfunction "4_4") (pintype "passive"))
      (node (ref "IF_N") (pin "5") (pinfunction "5_5") (pintype "passive"))
      (node (ref "IF_P") (pin "2") (pinfunction "2_2") (pintype "passive"))
      (node (ref "IF_P") (pin "3") (pinfunction "3_3") (pintype "passive"))
      (node (ref "IF_P") (pin "4") (pinfunction "4_4") (pintype "passive"))
      (node (ref "IF_P") (pin "5") (pinfunction "5_5") (pintype "passive"))
      (node (ref "J1") (pin "G") (pinfunction "GND_G") (pintype "passive"))
      (node (ref "J1") (pin "P") (pinfunction "SHELL_P") (pintype "passive"))
      (node (ref "LO_N") (pin "2") (pinfunction "2_2") (pintype "passive"))
      (node (ref "LO_N") (pin "3") (pinfunction "3_3") (pintype "passive"))
      (node (ref "LO_N") (pin "4") (pinfunction "4_4") (pintype "passive"))
      (node (ref "LO_N") (pin "5") (pinfunction "5_5") (pintype "passive"))
      (node (ref "LO_P") (pin "2") (pinfunction "2_2") (pintype "passive"))
      (node (ref "LO_P") (pin "3") (pinfunction "3_3") (pintype "passive"))
      (node (ref "LO_P") (pin "4") (pinfunction "4_4") (pintype "passive"))
      (node (ref "LO_P") (pin "5") (pinfunction "5_5") (pintype "passive"))
      (node (ref "P1") (pin "2") (pinfunction "2_2") (pintype "passive"))
      (node (ref "P3") (pin "1") (pinfunction "1_1") (pintype "passive"))
      (node (ref "P4") (pin "1") (pinfunction "1_1") (pintype "passive"))
      (node (ref "P5") (pin "8") (pinfunction "8_8") (pintype "passive"))
      (node (ref "P6") (pin "5") (pinfunction "5_5") (pintype "passive"))
      (node (ref "R1") (pin "1") (pinfunction "1_1") (pintype "passive"))
      (node (ref "R12") (pin "1") (pinfunction "1_1") (pintype "passive"))
      (node (ref "R2") (pin "1") (pinfunction "1_1") (pintype "passive"))
      (node (ref "R3") (pin "1") (pinfunction "1_1") (pintype "passive"))
      (node (ref "R4") (pin "1") (pinfunction "1_1") (pintype "passive"))
      (node (ref "RF_OUT_N") (pin "2") (pinfunction "2_2") (pintype "passive"))
      (node (ref "RF_OUT_N") (pin "3") (pinfunction "3_3") (pintype "passive"))
      (node (ref "RF_OUT_N") (pin "4") (pinfunction "4_4") (pintype "passive"))
      (node (ref "RF_OUT_N") (pin "5") (pinfunction "5_5") (pintype "passive"))
      (node (ref "RF_OUT_P") (pin "2") (pinfunction "2_2") (pintype "passive"))
      (node (ref "RF_OUT_P") (pin "3") (pinfunction "3_3") (pintype "passive"))
      (node (ref "RF_OUT_P") (pin "4") (pinfunction "4_4") (pintype "passive"))
      (node (ref "RF_OUT_P") (pin "5") (pinfunction "5_5") (pintype "passive"))
      (node (ref "U1") (pin "19") (pinfunction "AGND_19") (pintype "passive"))
      (node (ref "U1") (pin "29") (pinfunction "AGND_29") (pintype "passive"))
      (node (ref "U1") (pin "33") (pinfunction "EP(GND)_33") (pintype "passive"))
      (node (ref "U1") (pin "4") (pinfunction "AGND_4") (pintype "passive"))
      (node (ref "U1") (pin "6") (pinfunction "AGND_6") (pintype "passive"))
      (node (ref "U1") (pin "8") (pinfunction "AGND_8") (pintype "passive"))
      (node (ref "U2") (pin "5") (pinfunction "GND_5") (pintype "passive"))
      (node (ref "U3") (pin "6") (pinfunction "GND_6") (pintype "passive"))
      (node (ref "U4") (pin "6") (pinfunction "GND_6") (pintype "passive"))
      (node (ref "U5") (pin "10") (pinfunction "T/R2_10") (pintype "passive"))
      (node (ref "U5") (pin "8") (pinfunction "GND_8") (pintype "passive"))
    )
    (net (code "25") (name "Net-(C1-Pad2)") (class "Default")
      (node (ref "C1") (pin "2") (pinfunction "2_2") (pintype "passive"))
      (node (ref "IF_N") (pin "1") (pinfunction "1_1") (pintype "passive"))
    )
    (net (code "26") (name "Net-(C2-Pad2)") (class "Default")
      (node (ref "C2") (pin "2") (pinfunction "2_2") (pintype "passive"))
      (node (ref "IF_P") (pin "1") (pinfunction "1_1") (pintype "passive"))
    )
    (net (code "27") (name "Net-(U1-ALM*)") (class "Default")
      (node (ref "R13") (pin "1") (pinfunction "1_1") (pintype "passive"))
      (node (ref "U1") (pin "32") (pinfunction "ALM*_32") (pintype "passive"))
    )
    (net (code "28") (name "Net-(U1-IFIN)") (class "Default")
      (node (ref "C1") (pin "1") (pinfunction "1_1") (pintype "passive"))
      (node (ref "U1") (pin "18") (pinfunction "IFIN_18") (pintype "passive"))
    )
    (net (code "29") (name "Net-(U1-IFIP)") (class "Default")
      (node (ref "C2") (pin "1") (pinfunction "1_1") (pintype "passive"))
      (node (ref "U1") (pin "20") (pinfunction "IFIP_20") (pintype "passive"))
    )
    (net (code "30") (name "Net-(U1-PWDN)") (class "Default")
      (node (ref "P2") (pin "2") (pinfunction "2_2") (pintype "passive"))
      (node (ref "U1") (pin "16") (pinfunction "PWDN_16") (pintype "passive"))
    )
    (net (code "31") (name "Net-(U1-RST*)") (class "Default")
      (node (ref "P1") (pin "1") (pinfunction "1_1") (pintype "passive"))
      (node (ref "R5") (pin "1") (pinfunction "1_1") (pintype "passive"))
      (node (ref "U1") (pin "17") (pinfunction "RST*_17") (pintype "passive"))
    )
    (net (code "32") (name "Net-(U1-SCLK)") (class "Default")
      (node (ref "R9") (pin "1") (pinfunction "1_1") (pintype "passive"))
      (node (ref "U1") (pin "24") (pinfunction "SCLK_24") (pintype "passive"))
    )
    (net (code "33") (name "Net-(U1-SDIN)") (class "Default")
      (node (ref "R8") (pin "1") (pinfunction "1_1") (pintype "passive"))
      (node (ref "U1") (pin "23") (pinfunction "SDIN_23") (pintype "passive"))
    )
    (net (code "34") (name "Net-(U1-SDTO)") (class "Default")
      (node (ref "R7") (pin "1") (pinfunction "1_1") (pintype "passive"))
      (node (ref "U1") (pin "25") (pinfunction "SDTO_25") (pintype "passive"))
    )
    (net (code "35") (name "Net-(U1-SEN*)") (class "Default")
      (node (ref "R6") (pin "1") (pinfunction "1_1") (pintype "passive"))
      (node (ref "U1") (pin "26") (pinfunction "SEN*_26") (pintype "passive"))
    )
    (net (code "36") (name "Net-(U1-VATT)") (class "Default")
      (node (ref "C3") (pin "1") (pinfunction "1_1") (pintype "passive"))
      (node (ref "R10") (pin "2") (pinfunction "2_2") (pintype "passive"))
      (node (ref "U1") (pin "10") (pinfunction "VATT_10") (pintype "passive"))
    )
    (net (code "37") (name "Net-(U1-VDET)") (class "Default")
      (node (ref "C4") (pin "1") (pinfunction "1_1") (pintype "passive"))
      (node (ref "R11") (pin "2") (pinfunction "2_2") (pintype "passive"))
      (node (ref "U1") (pin "1") (pinfunction "VDET_1") (pintype "passive"))
    )
    (net (code "38") (name "Net-(U2-VOUT)") (class "Default")
      (node (ref "R16") (pin "2") (pinfunction "2_2") (pintype "passive"))
      (node (ref "U2") (pin "6") (pinfunction "VOUT_6") (pintype "passive"))
    )
    (net (code "39") (name "Net-(U3-SENSE)") (class "Default")
      (node (ref "C17") (pin "1") (pinfunction "1_1") (pintype "passive"))
      (node (ref "R14") (pin "2") (pinfunction "2_2") (pintype "passive"))
      (node (ref "U3") (pin "1") (pinfunction "VOUT_1") (pintype "passive"))
      (node (ref "U3") (pin "2") (pinfunction "VOUT_2") (pintype "passive"))
      (node (ref "U3") (pin "3") (pinfunction "SENSE_3") (pintype "passive"))
    )
    (net (code "40") (name "Net-(U3-SS)") (class "Default")
      (node (ref "C19") (pin "1") (pinfunction "1_1") (pintype "passive"))
      (node (ref "U3") (pin "4") (pinfunction "SS_4") (pintype "passive"))
    )
    (net (code "41") (name "Net-(U4-SENSE)") (class "Default")
      (node (ref "C26") (pin "1") (pinfunction "1_1") (pintype "passive"))
      (node (ref "R15") (pin "2") (pinfunction "2_2") (pintype "passive"))
      (node (ref "U4") (pin "1") (pinfunction "VOUT_1") (pintype "passive"))
      (node (ref "U4") (pin "2") (pinfunction "VOUT_2") (pintype "passive"))
      (node (ref "U4") (pin "3") (pinfunction "SENSE_3") (pintype "passive"))
    )
    (net (code "42") (name "Net-(U4-SS)") (class "Default")
      (node (ref "C28") (pin "1") (pinfunction "1_1") (pintype "passive"))
      (node (ref "U4") (pin "4") (pinfunction "SS_4") (pintype "passive"))
    )
    (net (code "43") (name "Net-(U5-A0)") (class "Default")
      (node (ref "R19") (pin "1") (pinfunction "1_1") (pintype "passive"))
      (node (ref "U5") (pin "3") (pinfunction "A0_3") (pintype "passive"))
    )
    (net (code "44") (name "Net-(U5-OE)") (class "Default")
      (node (ref "R17") (pin "1") (pinfunction "1_1") (pintype "passive"))
      (node (ref "R18") (pin "1") (pinfunction "1_1") (pintype "passive"))
      (node (ref "R19") (pin "2") (pinfunction "2_2") (pintype "passive"))
      (node (ref "U5") (pin "9") (pinfunction "OE_9") (pintype "passive"))
    )
    (net (code "45") (name "unconnected-(J1-CC1-PadA5)") (class "Default")
      (node (ref "J1") (pin "A5") (pinfunction "CC1_A5") (pintype "passive+no_connect"))
    )
    (net (code "46") (name "unconnected-(J1-CC2-PadB5)") (class "Default")
      (node (ref "J1") (pin "B5") (pinfunction "CC2_B5") (pintype "passive+no_connect"))
    )
    (net (code "47") (name "unconnected-(J1-DN1-PadA7)") (class "Default")
      (node (ref "J1") (pin "A7") (pinfunction "DN1_A7") (pintype "passive+no_connect"))
    )
    (net (code "48") (name "unconnected-(J1-DN2-PadB7)") (class "Default")
      (node (ref "J1") (pin "B7") (pinfunction "DN2_B7") (pintype "passive+no_connect"))
    )
    (net (code "49") (name "unconnected-(J1-DP1-PadA6)") (class "Default")
      (node (ref "J1") (pin "A6") (pinfunction "DP1_A6") (pintype "passive+no_connect"))
    )
    (net (code "50") (name "unconnected-(J1-DP2-PadB6)") (class "Default")
      (node (ref "J1") (pin "B6") (pinfunction "DP2_B6") (pintype "passive+no_connect"))
    )
    (net (code "51") (name "unconnected-(J1-SBU1-PadA8)") (class "Default")
      (node (ref "J1") (pin "A8") (pinfunction "SBU1_A8") (pintype "passive+no_connect"))
    )
    (net (code "52") (name "unconnected-(J1-SBU2-PadB8)") (class "Default")
      (node (ref "J1") (pin "B8") (pinfunction "SBU2_B8") (pintype "passive+no_connect"))
    )
    (net (code "53") (name "unconnected-(R12-Pad2)") (class "Default")
      (node (ref "R12") (pin "2") (pinfunction "2_2") (pintype "passive"))
    )
  )
)
